# DDS.net
KiCad netlist of a schematic drawn in Altium Designer
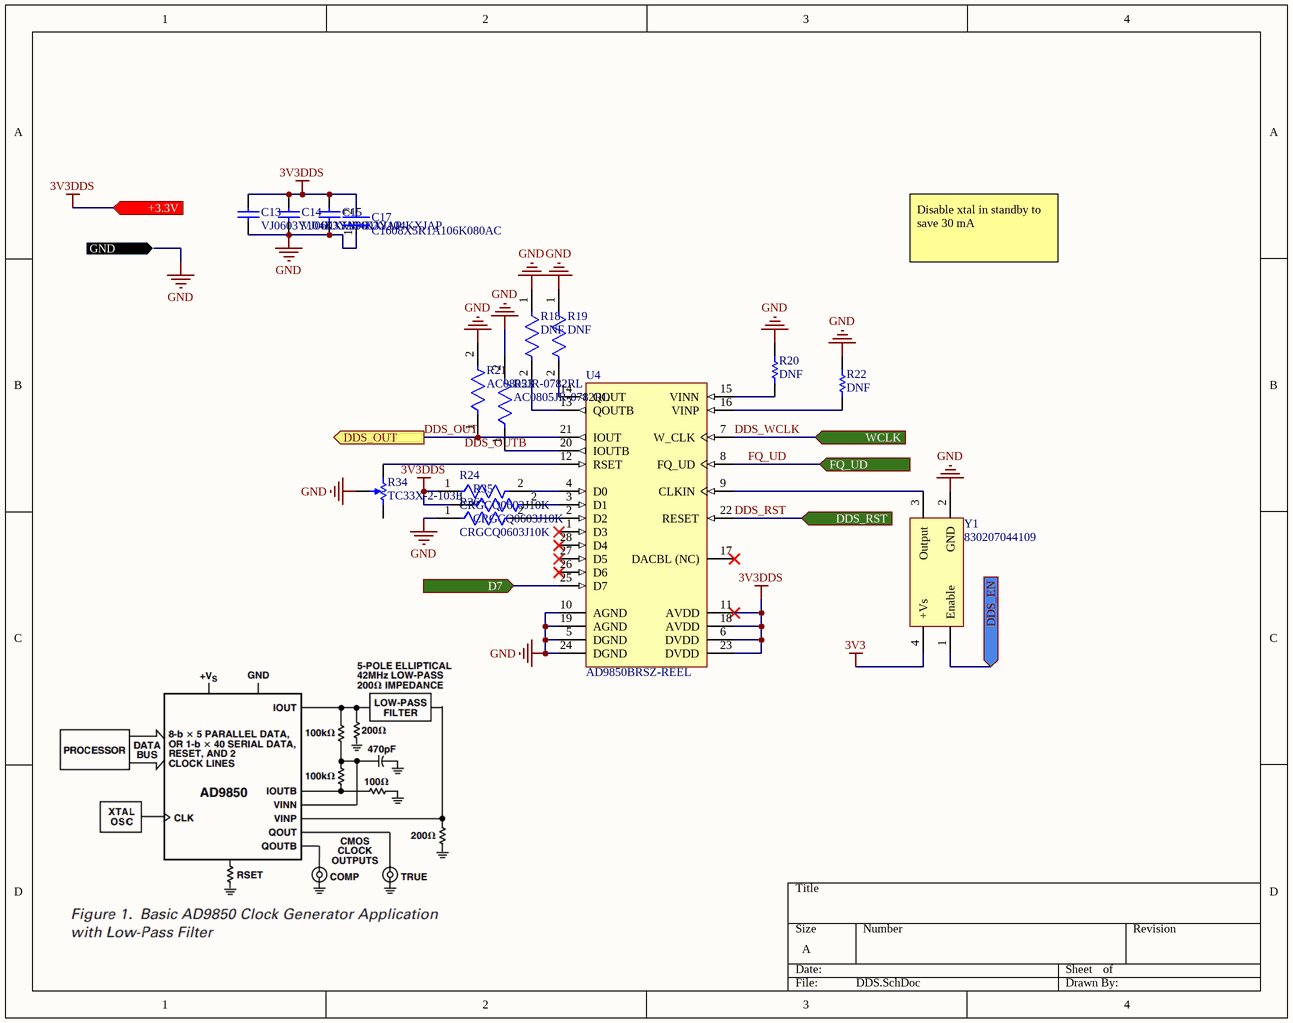
[diagram p0: DDS.SchDoc]

(export (version "E")
  (design (tool "Eeschema 10.0.6"))
  (components
    (comp (ref "C13")
      (value "VJ0603Y104KXJAP")
      (footprint "CAPC1608X92X38NL15T08")
      (fields (field (name "MANUFACTURER") "Vitramon"))
      (libsource (lib "Altium Content Vault") (part "CAP"))
    )
    (comp (ref "C14")
      (value "VJ0603Y104KXJAP")
      (footprint "CAPC1608X92X38NL15T08")
      (fields (field (name "MANUFACTURER") "Vitramon"))
      (libsource (lib "Altium Content Vault") (part "CAP"))
    )
    (comp (ref "C15")
      (value "VJ0603Y104KXJAP")
      (footprint "CAPC1608X92X38NL15T08")
      (fields (field (name "MANUFACTURER") "Vitramon"))
      (libsource (lib "Altium Content Vault") (part "CAP"))
    )
    (comp (ref "C17")
      (value "C1608X5R1A106K080AC")
      (footprint "FP-C1608-080-0_1-MFG")
      (description "Multilayer Ceramic Capacitors 10μF ±10% 10V X5R SMD 0603")
      (fields (field (name "VOLTAGE") "10V") (field (name "TOLERANCE") "10%"))
      (libsource (lib "Altium Content Vault") (part "236180d848d6139a670b325ea6854c9"))
    )
    (comp (ref "R18")
      (value "DNF")
      (footprint "FP-RMCF0603-IPC_B")
      (description "0Ω ±0 0.1W 0603 Thick Film Chip Resistor AEC-Q200 compliant")
      (libsource (lib "Altium Content Vault") (part "1029c3af85768c4190bb7ad29bc67b5"))
    )
    (comp (ref "R19")
      (value "DNF")
      (footprint "FP-RMCF0603-IPC_B")
      (description "0Ω ±0 0.1W 0603 Thick Film Chip Resistor AEC-Q200 compliant")
      (libsource (lib "Altium Content Vault") (part "1029c3af85768c4190bb7ad29bc67b5"))
    )
    (comp (ref "R20")
      (value "DNF")
      (footprint "RESC0603(1608)_N")
      (description "100K 0.1W 1% 0603 (1608 Metric)  SMD")
      (fields (field (name "POWER") "0.1 W") (field (name "TOLERANCE") "1 %"))
      (libsource (lib "Altium Content Vault") (part "RES"))
    )
    (comp (ref "R21")
      (value "AC0805JR-0782RL")
      (footprint "FP-AC0805-MFG")
      (description "RES SMD 82 OHM 5% 1/8W 0805")
      (fields (field (name "TOLERANCE") "0.05") (field (name "MANUFACTURER") "Yageo"))
      (libsource (lib "Altium Content Vault") (part "1029c3af85768c4190bb7ad29bc67b5"))
    )
    (comp (ref "R22")
      (value "DNF")
      (footprint "RESC0603(1608)_N")
      (description "100K 0.1W 1% 0603 (1608 Metric)  SMD")
      (fields (field (name "POWER") "0.1 W") (field (name "TOLERANCE") "1 %"))
      (libsource (lib "Altium Content Vault") (part "RES"))
    )
    (comp (ref "R23")
      (value "AC0805JR-0782RL")
      (footprint "FP-AC0805-MFG")
      (description "RES SMD 82 OHM 5% 1/8W 0805")
      (fields (field (name "TOLERANCE") "0.05") (field (name "MANUFACTURER") "Yageo"))
      (libsource (lib "Altium Content Vault") (part "1029c3af85768c4190bb7ad29bc67b5"))
    )
    (comp (ref "R24")
      (value "CRGCQ0603J10K")
      (footprint "FP-CRGCQ0603-IPC_C")
      (description "CRGCQ 0603 10K 5%")
      (fields
        (field (name "TOLERANCE") "0.05")
        (field (name "OCTOPART") "https://octopart.com/crgcq0603j10k-te+connectivity-91018097")
      )
      (libsource (lib "Altium Content Vault") (part "1029c3af85768c4190bb7ad29bc67b5"))
    )
    (comp (ref "R34")
      (value "TC33X-2-103E")
      (footprint "BOUR-TC33X-2_V")
      (description "Trimming Potentiometer, 10000 Ohm, -40 to 100 degC, 3-Pin SMD, RoHS, Tape and Reel")
      (fields (field (name "TOLERANCE") "25%") (field (name "MANUFACTURER") "Bourns"))
      (libsource (lib "Altium Content Vault") (part "RES-ADJ-3_A"))
    )
    (comp (ref "R35")
      (value "CRGCQ0603J10K")
      (footprint "FP-CRGCQ0603-IPC_C")
      (description "CRGCQ 0603 10K 5%")
      (fields
        (field (name "TOLERANCE") "0.05")
        (field (name "OCTOPART") "https://octopart.com/crgcq0603j10k-te+connectivity-91018097")
      )
      (libsource (lib "Altium Content Vault") (part "1029c3af85768c4190bb7ad29bc67b5"))
    )
    (comp (ref "R36")
      (value "CRGCQ0603J10K")
      (footprint "FP-CRGCQ0603-IPC_C")
      (description "CRGCQ 0603 10K 5%")
      (fields
        (field (name "TOLERANCE") "0.05")
        (field (name "OCTOPART") "https://octopart.com/crgcq0603j10k-te+connectivity-91018097")
      )
      (libsource (lib "Altium Content Vault") (part "1029c3af85768c4190bb7ad29bc67b5"))
    )
    (comp (ref "U4")
      (value "AD9850BRSZ-REEL")
      (footprint "ADI-RS-28_N")
      (description "CMOS, 125 MHz Complete DDS Synthesizer, 10-Bit, Parallel, Serial, RS-28, 1500 Reel, Pb-Free")
      (libsource (lib "Altium Content Vault") (part "ADI-AD9850-RS-28"))
    )
    (comp (ref "Y1")
      (value "830207044109")
      (footprint "WE-SPXO_CFPS-39")
      (description "830207044109 WE-SPXO Crystal Oscillator")
      (libsource (lib "Altium Content Vault") (part "WE-SPXO_CFPS-39"))
    )
  )
  (nets
    (net (code "1") (name "/D7") (class "Default")
      (node (ref "U4") (pin "25") (pinfunction "D7_25") (pintype "input"))
    )
    (net (code "2") (name "/DDS_EN") (class "Default")
      (node (ref "Y1") (pin "1") (pinfunction "Enable_1") (pintype "passive"))
    )
    (net (code "3") (name "/DDS_OUT") (class "Default")
      (node (ref "R21") (pin "1") (pinfunction "1_1") (pintype "passive"))
      (node (ref "U4") (pin "21") (pinfunction "IOUT_21") (pintype "output"))
    )
    (net (code "5") (name "/DDS_RST") (class "Default")
      (node (ref "U4") (pin "22") (pinfunction "RESET_22") (pintype "input"))
    )
    (net (code "6") (name "/DDS_WCLK") (class "Default")
      (node (ref "U4") (pin "7") (pinfunction "W_CLK_7") (pintype "input"))
    )
    (net (code "7") (name "/FQ_UD") (class "Default")
      (node (ref "U4") (pin "8") (pinfunction "FQ_UD_8") (pintype "input"))
    )
    (net (code "8") (name "3V3") (class "Default")
      (node (ref "Y1") (pin "4") (pinfunction "+Vs_4") (pintype "passive"))
    )
    (net (code "9") (name "3V3DDS") (class "Default")
      (node (ref "C13") (pin "2") (pinfunction "2_2") (pintype "passive"))
      (node (ref "C14") (pin "2") (pinfunction "2_2") (pintype "passive"))
      (node (ref "C15") (pin "2") (pinfunction "2_2") (pintype "passive"))
      (node (ref "C17") (pin "2") (pinfunction "2_2") (pintype "passive"))
      (node (ref "R24") (pin "1") (pinfunction "1_1") (pintype "passive"))
      (node (ref "R35") (pin "1") (pinfunction "1_1") (pintype "passive"))
      (node (ref "U4") (pin "11") (pinfunction "AVDD_11") (pintype "power_in"))
      (node (ref "U4") (pin "18") (pinfunction "AVDD_18") (pintype "power_in"))
      (node (ref "U4") (pin "23") (pinfunction "DVDD_23") (pintype "power_in"))
      (node (ref "U4") (pin "6") (pinfunction "DVDD_6") (pintype "power_in"))
    )
    (net (code "10") (name "GND") (class "Default")
      (node (ref "C13") (pin "1") (pinfunction "1_1") (pintype "passive"))
      (node (ref "C14") (pin "1") (pinfunction "1_1") (pintype "passive"))
      (node (ref "C15") (pin "1") (pinfunction "1_1") (pintype "passive"))
      (node (ref "C17") (pin "1") (pinfunction "1_1") (pintype "passive"))
      (node (ref "R18") (pin "1") (pinfunction "1_1") (pintype "passive"))
      (node (ref "R19") (pin "1") (pinfunction "1_1") (pintype "passive"))
      (node (ref "R20") (pin "2") (pinfunction "2_2") (pintype "passive"))
      (node (ref "R21") (pin "2") (pinfunction "2_2") (pintype "passive"))
      (node (ref "R22") (pin "2") (pinfunction "2_2") (pintype "passive"))
      (node (ref "R23") (pin "2") (pinfunction "2_2") (pintype "passive"))
      (node (ref "R34") (pin "2") (pinfunction "2_2") (pintype "passive"))
      (node (ref "R36") (pin "1") (pinfunction "1_1") (pintype "passive"))
      (node (ref "U4") (pin "10") (pinfunction "AGND_10") (pintype "power_in"))
      (node (ref "U4") (pin "19") (pinfunction "AGND_19") (pintype "power_in"))
      (node (ref "U4") (pin "24") (pinfunction "DGND_24") (pintype "power_in"))
      (node (ref "U4") (pin "5") (pinfunction "DGND_5") (pintype "power_in"))
      (node (ref "Y1") (pin "2") (pinfunction "GND_2") (pintype "passive"))
    )
    (net (code "11") (name "Net-(U4-CLKIN)") (class "Default")
      (node (ref "U4") (pin "9") (pinfunction "CLKIN_9") (pintype "input"))
      (node (ref "Y1") (pin "3") (pinfunction "Output_3") (pintype "passive"))
    )
    (net (code "12") (name "Net-(U4-D0)") (class "Default")
      (node (ref "R24") (pin "2") (pinfunction "2_2") (pintype "passive"))
      (node (ref "U4") (pin "4") (pinfunction "D0_4") (pintype "input"))
    )
    (net (code "13") (name "Net-(U4-D1)") (class "Default")
      (node (ref "R35") (pin "2") (pinfunction "2_2") (pintype "passive"))
      (node (ref "U4") (pin "3") (pinfunction "D1_3") (pintype "input"))
    )
    (net (code "14") (name "Net-(U4-D2)") (class "Default")
      (node (ref "R36") (pin "2") (pinfunction "2_2") (pintype "passive"))
      (node (ref "U4") (pin "2") (pinfunction "D2_2") (pintype "input"))
    )
    (net (code "15") (name "Net-(U4-IOUTB)") (class "Default")
      (node (ref "R23") (pin "1") (pinfunction "1_1") (pintype "passive"))
      (node (ref "U4") (pin "20") (pinfunction "IOUTB_20") (pintype "output"))
    )
    (net (code "16") (name "Net-(U4-QOUT)") (class "Default")
      (node (ref "R19") (pin "2") (pinfunction "2_2") (pintype "passive"))
      (node (ref "U4") (pin "14") (pinfunction "QOUT_14") (pintype "output"))
    )
    (net (code "17") (name "Net-(U4-QOUTB)") (class "Default")
      (node (ref "R18") (pin "2") (pinfunction "2_2") (pintype "passive"))
      (node (ref "U4") (pin "13") (pinfunction "QOUTB_13") (pintype "output"))
    )
    (net (code "18") (name "Net-(U4-RSET)") (class "Default")
      (node (ref "R34") (pin "1") (pinfunction "1_1") (pintype "passive"))
      (node (ref "U4") (pin "12") (pinfunction "RSET_12") (pintype "input"))
    )
    (net (code "19") (name "Net-(U4-VINN)") (class "Default")
      (node (ref "R20") (pin "1") (pinfunction "1_1") (pintype "passive"))
      (node (ref "U4") (pin "15") (pinfunction "VINN_15") (pintype "input"))
    )
    (net (code "20") (name "Net-(U4-VINP)") (class "Default")
      (node (ref "R22") (pin "1") (pinfunction "1_1") (pintype "passive"))
      (node (ref "U4") (pin "16") (pinfunction "VINP_16") (pintype "input"))
    )
    (net (code "21") (name "unconnected-(R34-Pad3)") (class "Default")
      (node (ref "R34") (pin "3") (pinfunction "3_3") (pintype "passive"))
    )
    (net (code "22") (name "unconnected-(U4-D3-Pad1)") (class "Default")
      (node (ref "U4") (pin "1") (pinfunction "D3_1") (pintype "input+no_connect"))
    )
    (net (code "23") (name "unconnected-(U4-D4-Pad28)") (class "Default")
      (node (ref "U4") (pin "28") (pinfunction "D4_28") (pintype "input+no_connect"))
    )
    (net (code "24") (name "unconnected-(U4-D5-Pad27)") (class "Default")
      (node (ref "U4") (pin "27") (pinfunction "D5_27") (pintype "input+no_connect"))
    )
    (net (code "25") (name "unconnected-(U4-D6-Pad26)") (class "Default")
      (node (ref "U4") (pin "26") (pinfunction "D6_26") (pintype "input+no_connect"))
    )
    (net (code "26") (name "unconnected-(U4-DACBL_(NC)-Pad17)") (class "Default")
      (node (ref "U4") (pin "17") (pinfunction "DACBL_(NC)_17") (pintype "passive+no_connect"))
    )
  )
)
